# IO_Boardv3_RelayAlarm.net
KiCad netlist of a schematic drawn in Altium Designer
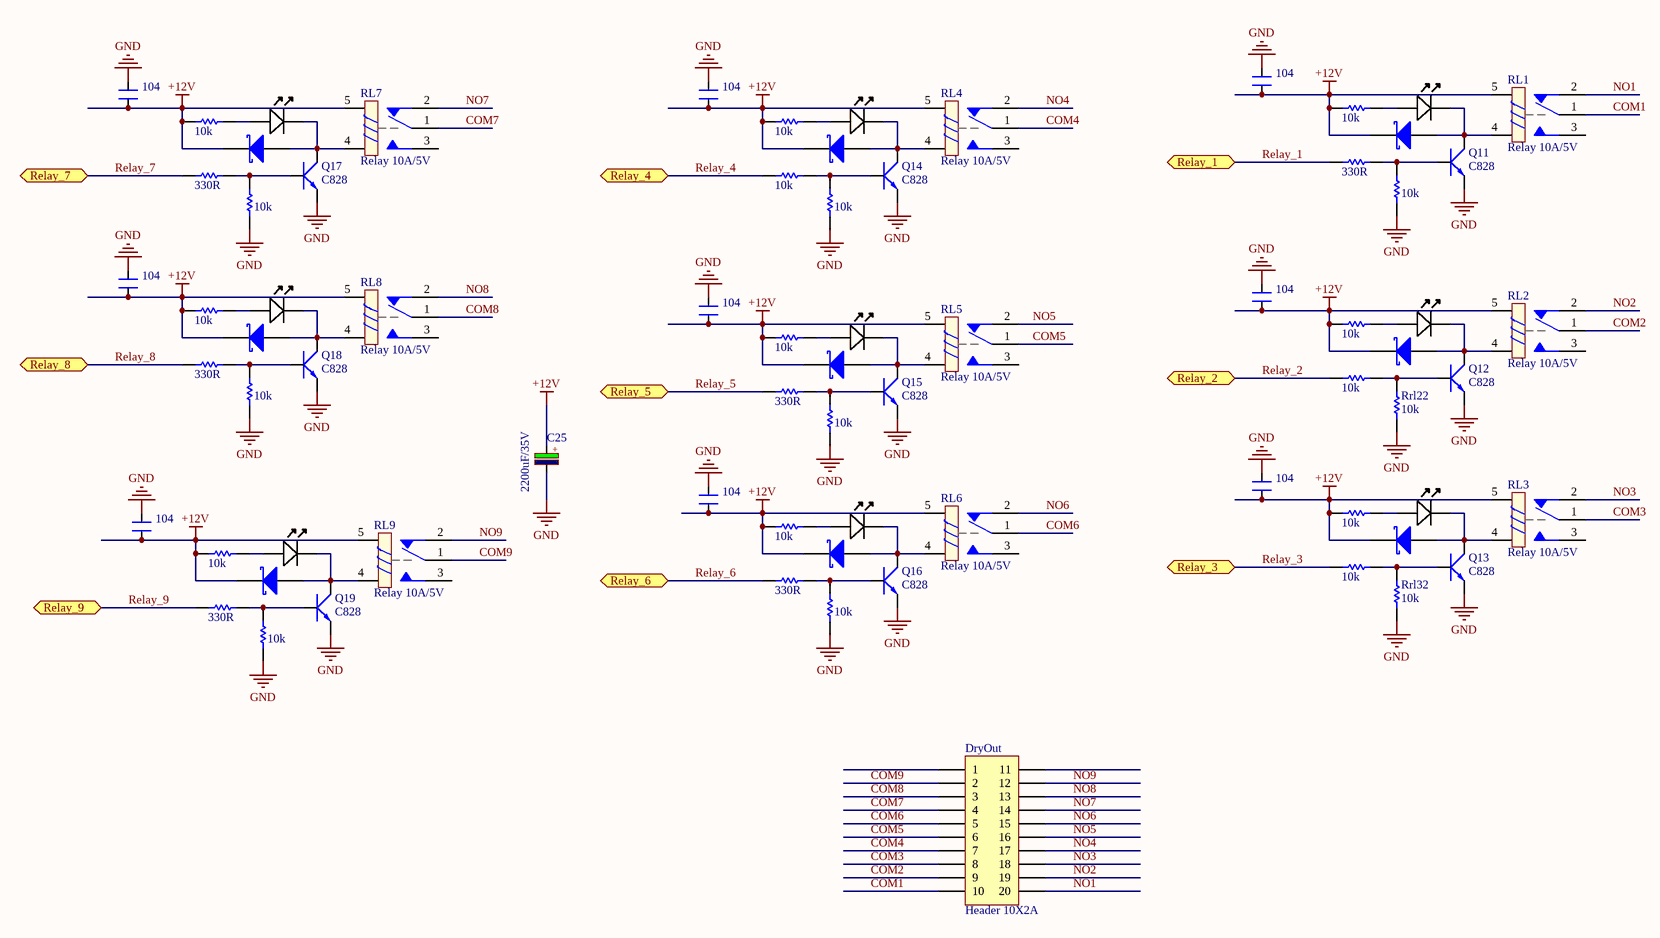
[diagram p0: IO_Boardv3_RelayAlarm.SchDoc]

(export (version "E")
  (design (tool "Eeschema 10.0.6"))
  (components
    (comp (ref "C25")
      (value "2200uF/35V")
      (footprint "heromap:CP_1000uF_25V")
      (description "Cap 1000uF/16V - 220uF/50V")
      (libsource (lib "heromap") (part "CP4"))
    )
    (comp (ref "Crl1")
      (value "104")
      (footprint "CAPC2012N_F")
      (fields (field (name "Comment") "CAP NP"))
      (libsource (lib "Tuan") (part "CAP NP"))
    )
    (comp (ref "Crl2")
      (value "104")
      (footprint "CAPC2012N_F")
      (fields (field (name "Comment") "CAP NP"))
      (libsource (lib "Tuan") (part "CAP NP"))
    )
    (comp (ref "Crl3")
      (value "104")
      (footprint "CAPC2012N_F")
      (fields (field (name "Comment") "CAP NP"))
      (libsource (lib "Tuan") (part "CAP NP"))
    )
    (comp (ref "Crl4")
      (value "104")
      (footprint "CAPC2012N_F")
      (fields (field (name "Comment") "CAP NP"))
      (libsource (lib "Tuan") (part "CAP NP"))
    )
    (comp (ref "Crl5")
      (value "104")
      (footprint "CAPC2012N_F")
      (fields (field (name "Comment") "CAP NP"))
      (libsource (lib "Tuan") (part "CAP NP"))
    )
    (comp (ref "Crl6")
      (value "104")
      (footprint "CAPC2012N_F")
      (fields (field (name "Comment") "CAP NP"))
      (libsource (lib "Tuan") (part "CAP NP"))
    )
    (comp (ref "Crl7")
      (value "104")
      (footprint "CAPC2012N_F")
      (fields (field (name "Comment") "CAP NP"))
      (libsource (lib "Tuan") (part "CAP NP"))
    )
    (comp (ref "Crl8")
      (value "104")
      (footprint "CAPC2012N_F")
      (fields (field (name "Comment") "CAP NP"))
      (libsource (lib "Tuan") (part "CAP NP"))
    )
    (comp (ref "Crl9")
      (value "104")
      (footprint "CAPC2012N_F")
      (fields (field (name "Comment") "CAP NP"))
      (libsource (lib "Tuan") (part "CAP NP"))
    )
    (comp (ref "D11") (value "Diode") (footprint "DO-214AC") (libsource (lib "Tuan") (part "Diode")))
    (comp (ref "D12") (value "Diode") (footprint "DO-214AC") (libsource (lib "Tuan") (part "Diode")))
    (comp (ref "D13") (value "Diode") (footprint "DO-214AC") (libsource (lib "Tuan") (part "Diode")))
    (comp (ref "D14") (value "Diode") (footprint "DO-214AC") (libsource (lib "Tuan") (part "Diode")))
    (comp (ref "D15") (value "Diode") (footprint "DO-214AC") (libsource (lib "Tuan") (part "Diode")))
    (comp (ref "D16") (value "Diode") (footprint "DO-214AC") (libsource (lib "Tuan") (part "Diode")))
    (comp (ref "D17") (value "Diode") (footprint "DO-214AC") (libsource (lib "Tuan") (part "Diode")))
    (comp (ref "D18") (value "Diode") (footprint "DO-214AC") (libsource (lib "Tuan") (part "Diode")))
    (comp (ref "D19") (value "Diode") (footprint "DO-214AC") (libsource (lib "Tuan") (part "Diode")))
    (comp (ref "DryOut")
      (value "Header 10X2A")
      (footprint "heromap:HDR2X10_CEN")
      (description "Header, 10-Pin, Dual row")
      (fields (field (name "PUBLISHER") "Altium Limited"))
      (libsource (lib "heromap") (part "Header 10X2A"))
    )
    (comp (ref "E1")
      (value "Blue")
      (footprint "LED-0805-A")
      (description "LED 0805 SMD Blue 100mcd 470nm")
      (libsource (lib "PBL - Light Sources") (part "LED_SMD_Blue_0805_100mcd"))
    )
    (comp (ref "E2")
      (value "Blue")
      (footprint "LED-0805-A")
      (description "LED 0805 SMD Blue 100mcd 470nm")
      (libsource (lib "PBL - Light Sources") (part "LED_SMD_Blue_0805_100mcd"))
    )
    (comp (ref "E3")
      (value "Blue")
      (footprint "LED-0805-A")
      (description "LED 0805 SMD Blue 100mcd 470nm")
      (libsource (lib "PBL - Light Sources") (part "LED_SMD_Blue_0805_100mcd"))
    )
    (comp (ref "E4")
      (value "Blue")
      (footprint "LED-0805-A")
      (description "LED 0805 SMD Blue 100mcd 470nm")
      (libsource (lib "PBL - Light Sources") (part "LED_SMD_Blue_0805_100mcd"))
    )
    (comp (ref "E5")
      (value "Blue")
      (footprint "LED-0805-A")
      (description "LED 0805 SMD Blue 100mcd 470nm")
      (libsource (lib "PBL - Light Sources") (part "LED_SMD_Blue_0805_100mcd"))
    )
    (comp (ref "E6")
      (value "Blue")
      (footprint "LED-0805-A")
      (description "LED 0805 SMD Blue 100mcd 470nm")
      (libsource (lib "PBL - Light Sources") (part "LED_SMD_Blue_0805_100mcd"))
    )
    (comp (ref "E7")
      (value "Blue")
      (footprint "LED-0805-A")
      (description "LED 0805 SMD Blue 100mcd 470nm")
      (libsource (lib "PBL - Light Sources") (part "LED_SMD_Blue_0805_100mcd"))
    )
    (comp (ref "E8")
      (value "Blue")
      (footprint "LED-0805-A")
      (description "LED 0805 SMD Blue 100mcd 470nm")
      (libsource (lib "PBL - Light Sources") (part "LED_SMD_Blue_0805_100mcd"))
    )
    (comp (ref "E9")
      (value "Blue")
      (footprint "LED-0805-A")
      (description "LED 0805 SMD Blue 100mcd 470nm")
      (libsource (lib "PBL - Light Sources") (part "LED_SMD_Blue_0805_100mcd"))
    )
    (comp (ref "Q11")
      (value "C828")
      (footprint "SOT23 TOP")
      (description "Transistor C828 C1815....")
      (libsource (lib "Tuan") (part "NPN"))
    )
    (comp (ref "Q12")
      (value "C828")
      (footprint "SOT23 TOP")
      (description "Transistor C828 C1815....")
      (libsource (lib "Tuan") (part "NPN"))
    )
    (comp (ref "Q13")
      (value "C828")
      (footprint "SOT23 TOP")
      (description "Transistor C828 C1815....")
      (libsource (lib "Tuan") (part "NPN"))
    )
    (comp (ref "Q14")
      (value "C828")
      (footprint "SOT23 TOP")
      (description "Transistor C828 C1815....")
      (libsource (lib "Tuan") (part "NPN"))
    )
    (comp (ref "Q15")
      (value "C828")
      (footprint "SOT23 TOP")
      (description "Transistor C828 C1815....")
      (libsource (lib "Tuan") (part "NPN"))
    )
    (comp (ref "Q16")
      (value "C828")
      (footprint "SOT23 TOP")
      (description "Transistor C828 C1815....")
      (libsource (lib "Tuan") (part "NPN"))
    )
    (comp (ref "Q17")
      (value "C828")
      (footprint "SOT23 TOP")
      (description "Transistor C828 C1815....")
      (libsource (lib "Tuan") (part "NPN"))
    )
    (comp (ref "Q18")
      (value "C828")
      (footprint "SOT23 TOP")
      (description "Transistor C828 C1815....")
      (libsource (lib "Tuan") (part "NPN"))
    )
    (comp (ref "Q19")
      (value "C828")
      (footprint "SOT23 TOP")
      (description "Transistor C828 C1815....")
      (libsource (lib "Tuan") (part "NPN"))
    )
    (comp (ref "RL1")
      (value "Relay 10A/5V")
      (footprint "RL_5PIN")
      (description "Relay SPDT,10A - 12VDC 5 Pin")
      (libsource (lib "syhaunguyen") (part "Relay 1"))
    )
    (comp (ref "RL2")
      (value "Relay 10A/5V")
      (footprint "RL_5PIN")
      (description "Relay SPDT,10A - 12VDC 5 Pin")
      (libsource (lib "syhaunguyen") (part "Relay 1"))
    )
    (comp (ref "RL3")
      (value "Relay 10A/5V")
      (footprint "RL_5PIN")
      (description "Relay SPDT,10A - 12VDC 5 Pin")
      (libsource (lib "syhaunguyen") (part "Relay 1"))
    )
    (comp (ref "RL4")
      (value "Relay 10A/5V")
      (footprint "RL_5PIN")
      (description "Relay SPDT,10A - 12VDC 5 Pin")
      (libsource (lib "syhaunguyen") (part "Relay 1"))
    )
    (comp (ref "RL5")
      (value "Relay 10A/5V")
      (footprint "RL_5PIN")
      (description "Relay SPDT,10A - 12VDC 5 Pin")
      (libsource (lib "syhaunguyen") (part "Relay 1"))
    )
    (comp (ref "RL6")
      (value "Relay 10A/5V")
      (footprint "RL_5PIN")
      (description "Relay SPDT,10A - 12VDC 5 Pin")
      (libsource (lib "syhaunguyen") (part "Relay 1"))
    )
    (comp (ref "RL7")
      (value "Relay 10A/5V")
      (footprint "RL_5PIN")
      (description "Relay SPDT,10A - 12VDC 5 Pin")
      (libsource (lib "syhaunguyen") (part "Relay 1"))
    )
    (comp (ref "RL8")
      (value "Relay 10A/5V")
      (footprint "RL_5PIN")
      (description "Relay SPDT,10A - 12VDC 5 Pin")
      (libsource (lib "syhaunguyen") (part "Relay 1"))
    )
    (comp (ref "RL9")
      (value "Relay 10A/5V")
      (footprint "RL_5PIN")
      (description "Relay SPDT,10A - 12VDC 5 Pin")
      (libsource (lib "syhaunguyen") (part "Relay 1"))
    )
    (comp (ref "Rl52")
      (value "10k")
      (footprint "RESC1608N_ZERO")
      (fields (field (name "Comment") "Res"))
      (libsource (lib "Tuan") (part "Res"))
    )
    (comp (ref "Rrl11")
      (value "330R")
      (footprint "RESC1608N_ZERO")
      (fields (field (name "Comment") "Res"))
      (libsource (lib "Tuan") (part "Res"))
    )
    (comp (ref "Rrl12")
      (value "10k")
      (footprint "RESC1608N_ZERO")
      (fields (field (name "Comment") "Res"))
      (libsource (lib "Tuan") (part "Res"))
    )
    (comp (ref "Rrl13")
      (value "10k")
      (footprint "RESC1608N_ZERO")
      (fields (field (name "Comment") "Res"))
      (libsource (lib "Tuan") (part "Res"))
    )
    (comp (ref "Rrl21")
      (value "10k")
      (footprint "RESC1608N_ZERO")
      (fields (field (name "Comment") "Res"))
      (libsource (lib "Tuan") (part "Res"))
    )
    (comp (ref "Rrl22")
      (value "10k")
      (footprint "RESC1608N_ZERO")
      (fields (field (name "Comment") "Res"))
      (libsource (lib "Tuan") (part "Res"))
    )
    (comp (ref "Rrl23")
      (value "10k")
      (footprint "RESC1608N_ZERO")
      (fields (field (name "Comment") "Res"))
      (libsource (lib "Tuan") (part "Res"))
    )
    (comp (ref "Rrl31")
      (value "10k")
      (footprint "RESC1608N_ZERO")
      (fields (field (name "Comment") "Res"))
      (libsource (lib "Tuan") (part "Res"))
    )
    (comp (ref "Rrl32")
      (value "10k")
      (footprint "RESC1608N_ZERO")
      (fields (field (name "Comment") "Res"))
      (libsource (lib "Tuan") (part "Res"))
    )
    (comp (ref "Rrl33")
      (value "10k")
      (footprint "RESC1608N_ZERO")
      (fields (field (name "Comment") "Res"))
      (libsource (lib "Tuan") (part "Res"))
    )
    (comp (ref "Rrl41")
      (value "10k")
      (footprint "RESC1608N_ZERO")
      (fields (field (name "Comment") "Res"))
      (libsource (lib "Tuan") (part "Res"))
    )
    (comp (ref "Rrl42")
      (value "10k")
      (footprint "RESC1608N_ZERO")
      (fields (field (name "Comment") "Res"))
      (libsource (lib "Tuan") (part "Res"))
    )
    (comp (ref "Rrl43")
      (value "10k")
      (footprint "RESC1608N_ZERO")
      (fields (field (name "Comment") "Res"))
      (libsource (lib "Tuan") (part "Res"))
    )
    (comp (ref "Rrl51")
      (value "330R")
      (footprint "RESC1608N_ZERO")
      (fields (field (name "Comment") "Res"))
      (libsource (lib "Tuan") (part "Res"))
    )
    (comp (ref "Rrl53")
      (value "10k")
      (footprint "RESC1608N_ZERO")
      (fields (field (name "Comment") "Res"))
      (libsource (lib "Tuan") (part "Res"))
    )
    (comp (ref "Rrl61")
      (value "330R")
      (footprint "RESC1608N_ZERO")
      (fields (field (name "Comment") "Res"))
      (libsource (lib "Tuan") (part "Res"))
    )
    (comp (ref "Rrl62")
      (value "10k")
      (footprint "RESC1608N_ZERO")
      (fields (field (name "Comment") "Res"))
      (libsource (lib "Tuan") (part "Res"))
    )
    (comp (ref "Rrl63")
      (value "10k")
      (footprint "RESC1608N_ZERO")
      (fields (field (name "Comment") "Res"))
      (libsource (lib "Tuan") (part "Res"))
    )
    (comp (ref "Rrl71")
      (value "330R")
      (footprint "RESC1608N_ZERO")
      (fields (field (name "Comment") "Res"))
      (libsource (lib "Tuan") (part "Res"))
    )
    (comp (ref "Rrl72")
      (value "10k")
      (footprint "RESC1608N_ZERO")
      (fields (field (name "Comment") "Res"))
      (libsource (lib "Tuan") (part "Res"))
    )
    (comp (ref "Rrl73")
      (value "10k")
      (footprint "RESC1608N_ZERO")
      (fields (field (name "Comment") "Res"))
      (libsource (lib "Tuan") (part "Res"))
    )
    (comp (ref "Rrl81")
      (value "330R")
      (footprint "RESC1608N_ZERO")
      (fields (field (name "Comment") "Res"))
      (libsource (lib "Tuan") (part "Res"))
    )
    (comp (ref "Rrl82")
      (value "10k")
      (footprint "RESC1608N_ZERO")
      (fields (field (name "Comment") "Res"))
      (libsource (lib "Tuan") (part "Res"))
    )
    (comp (ref "Rrl83")
      (value "10k")
      (footprint "RESC1608N_ZERO")
      (fields (field (name "Comment") "Res"))
      (libsource (lib "Tuan") (part "Res"))
    )
    (comp (ref "Rrl91")
      (value "330R")
      (footprint "RESC1608N_ZERO")
      (fields (field (name "Comment") "Res"))
      (libsource (lib "Tuan") (part "Res"))
    )
    (comp (ref "Rrl92")
      (value "10k")
      (footprint "RESC1608N_ZERO")
      (fields (field (name "Comment") "Res"))
      (libsource (lib "Tuan") (part "Res"))
    )
    (comp (ref "Rrl93")
      (value "10k")
      (footprint "RESC1608N_ZERO")
      (fields (field (name "Comment") "Res"))
      (libsource (lib "Tuan") (part "Res"))
    )
  )
  (nets
    (net (code "1") (name "+12V") (class "Default")
      (node (ref "C25") (pin "1") (pinfunction "1_1") (pintype "passive"))
      (node (ref "Crl1") (pin "1") (pinfunction "1_1") (pintype "passive"))
      (node (ref "Crl2") (pin "1") (pinfunction "1_1") (pintype "passive"))
      (node (ref "Crl3") (pin "1") (pinfunction "1_1") (pintype "passive"))
      (node (ref "Crl4") (pin "1") (pinfunction "1_1") (pintype "passive"))
      (node (ref "Crl5") (pin "1") (pinfunction "1_1") (pintype "passive"))
      (node (ref "Crl6") (pin "1") (pinfunction "1_1") (pintype "passive"))
      (node (ref "Crl7") (pin "1") (pinfunction "1_1") (pintype "passive"))
      (node (ref "Crl8") (pin "1") (pinfunction "1_1") (pintype "passive"))
      (node (ref "Crl9") (pin "1") (pinfunction "1_1") (pintype "passive"))
      (node (ref "D11") (pin "2") (pinfunction "K_2") (pintype "passive"))
      (node (ref "D12") (pin "2") (pinfunction "K_2") (pintype "passive"))
      (node (ref "D13") (pin "2") (pinfunction "K_2") (pintype "passive"))
      (node (ref "D14") (pin "2") (pinfunction "K_2") (pintype "passive"))
      (node (ref "D15") (pin "2") (pinfunction "K_2") (pintype "passive"))
      (node (ref "D16") (pin "2") (pinfunction "K_2") (pintype "passive"))
      (node (ref "D17") (pin "2") (pinfunction "K_2") (pintype "passive"))
      (node (ref "D18") (pin "2") (pinfunction "K_2") (pintype "passive"))
      (node (ref "D19") (pin "2") (pinfunction "K_2") (pintype "passive"))
      (node (ref "RL1") (pin "5") (pinfunction "5_5") (pintype "passive"))
      (node (ref "RL2") (pin "5") (pinfunction "5_5") (pintype "passive"))
      (node (ref "RL3") (pin "5") (pinfunction "5_5") (pintype "passive"))
      (node (ref "RL4") (pin "5") (pinfunction "5_5") (pintype "passive"))
      (node (ref "RL5") (pin "5") (pinfunction "5_5") (pintype "passive"))
      (node (ref "RL6") (pin "5") (pinfunction "5_5") (pintype "passive"))
      (node (ref "RL7") (pin "5") (pinfunction "5_5") (pintype "passive"))
      (node (ref "RL8") (pin "5") (pinfunction "5_5") (pintype "passive"))
      (node (ref "RL9") (pin "5") (pinfunction "5_5") (pintype "passive"))
      (node (ref "Rrl13") (pin "2") (pinfunction "2_2") (pintype "passive"))
      (node (ref "Rrl23") (pin "2") (pinfunction "2_2") (pintype "passive"))
      (node (ref "Rrl33") (pin "2") (pinfunction "2_2") (pintype "passive"))
      (node (ref "Rrl43") (pin "2") (pinfunction "2_2") (pintype "passive"))
      (node (ref "Rrl53") (pin "2") (pinfunction "2_2") (pintype "passive"))
      (node (ref "Rrl63") (pin "2") (pinfunction "2_2") (pintype "passive"))
      (node (ref "Rrl73") (pin "2") (pinfunction "2_2") (pintype "passive"))
      (node (ref "Rrl83") (pin "2") (pinfunction "2_2") (pintype "passive"))
      (node (ref "Rrl93") (pin "2") (pinfunction "2_2") (pintype "passive"))
    )
    (net (code "2") (name "/COM1") (class "Default")
      (node (ref "DryOut") (pin "10") (pinfunction "10_10") (pintype "passive"))
      (node (ref "RL1") (pin "1") (pinfunction "1_1") (pintype "passive"))
    )
    (net (code "3") (name "/COM2") (class "Default")
      (node (ref "DryOut") (pin "9") (pinfunction "9_9") (pintype "passive"))
      (node (ref "RL2") (pin "1") (pinfunction "1_1") (pintype "passive"))
    )
    (net (code "4") (name "/COM3") (class "Default")
      (node (ref "DryOut") (pin "8") (pinfunction "8_8") (pintype "passive"))
      (node (ref "RL3") (pin "1") (pinfunction "1_1") (pintype "passive"))
    )
    (net (code "5") (name "/COM4") (class "Default")
      (node (ref "DryOut") (pin "7") (pinfunction "7_7") (pintype "passive"))
      (node (ref "RL4") (pin "1") (pinfunction "1_1") (pintype "passive"))
    )
    (net (code "6") (name "/COM5") (class "Default")
      (node (ref "DryOut") (pin "6") (pinfunction "6_6") (pintype "passive"))
      (node (ref "RL5") (pin "1") (pinfunction "1_1") (pintype "passive"))
    )
    (net (code "7") (name "/COM6") (class "Default")
      (node (ref "DryOut") (pin "5") (pinfunction "5_5") (pintype "passive"))
      (node (ref "RL6") (pin "1") (pinfunction "1_1") (pintype "passive"))
    )
    (net (code "8") (name "/COM7") (class "Default")
      (node (ref "DryOut") (pin "4") (pinfunction "4_4") (pintype "passive"))
      (node (ref "RL7") (pin "1") (pinfunction "1_1") (pintype "passive"))
    )
    (net (code "9") (name "/COM8") (class "Default")
      (node (ref "DryOut") (pin "3") (pinfunction "3_3") (pintype "passive"))
      (node (ref "RL8") (pin "1") (pinfunction "1_1") (pintype "passive"))
    )
    (net (code "10") (name "/COM9") (class "Default")
      (node (ref "DryOut") (pin "2") (pinfunction "2_2") (pintype "passive"))
      (node (ref "RL9") (pin "1") (pinfunction "1_1") (pintype "passive"))
    )
    (net (code "11") (name "/NO1") (class "Default")
      (node (ref "DryOut") (pin "20") (pinfunction "20_20") (pintype "passive"))
      (node (ref "RL1") (pin "2") (pinfunction "2_2") (pintype "passive"))
    )
    (net (code "12") (name "/NO2") (class "Default")
      (node (ref "DryOut") (pin "19") (pinfunction "19_19") (pintype "passive"))
      (node (ref "RL2") (pin "2") (pinfunction "2_2") (pintype "passive"))
    )
    (net (code "13") (name "/NO3") (class "Default")
      (node (ref "DryOut") (pin "18") (pinfunction "18_18") (pintype "passive"))
      (node (ref "RL3") (pin "2") (pinfunction "2_2") (pintype "passive"))
    )
    (net (code "14") (name "/NO4") (class "Default")
      (node (ref "DryOut") (pin "17") (pinfunction "17_17") (pintype "passive"))
      (node (ref "RL4") (pin "2") (pinfunction "2_2") (pintype "passive"))
    )
    (net (code "15") (name "/NO5") (class "Default")
      (node (ref "DryOut") (pin "16") (pinfunction "16_16") (pintype "passive"))
      (node (ref "RL5") (pin "2") (pinfunction "2_2") (pintype "passive"))
    )
    (net (code "16") (name "/NO6") (class "Default")
      (node (ref "DryOut") (pin "15") (pinfunction "15_15") (pintype "passive"))
      (node (ref "RL6") (pin "2") (pinfunction "2_2") (pintype "passive"))
    )
    (net (code "17") (name "/NO7") (class "Default")
      (node (ref "DryOut") (pin "14") (pinfunction "14_14") (pintype "passive"))
      (node (ref "RL7") (pin "2") (pinfunction "2_2") (pintype "passive"))
    )
    (net (code "18") (name "/NO8") (class "Default")
      (node (ref "DryOut") (pin "13") (pinfunction "13_13") (pintype "passive"))
      (node (ref "RL8") (pin "2") (pinfunction "2_2") (pintype "passive"))
    )
    (net (code "19") (name "/NO9") (class "Default")
      (node (ref "DryOut") (pin "12") (pinfunction "12_12") (pintype "passive"))
      (node (ref "RL9") (pin "2") (pinfunction "2_2") (pintype "passive"))
    )
    (net (code "20") (name "/Relay_1") (class "Default")
      (node (ref "Rrl11") (pin "1") (pinfunction "1_1") (pintype "passive"))
    )
    (net (code "21") (name "/Relay_2") (class "Default")
      (node (ref "Rrl21") (pin "1") (pinfunction "1_1") (pintype "passive"))
    )
    (net (code "22") (name "/Relay_3") (class "Default")
      (node (ref "Rrl31") (pin "1") (pinfunction "1_1") (pintype "passive"))
    )
    (net (code "23") (name "/Relay_4") (class "Default")
      (node (ref "Rrl41") (pin "1") (pinfunction "1_1") (pintype "passive"))
    )
    (net (code "24") (name "/Relay_5") (class "Default")
      (node (ref "Rrl51") (pin "1") (pinfunction "1_1") (pintype "passive"))
    )
    (net (code "25") (name "/Relay_6") (class "Default")
      (node (ref "Rrl61") (pin "1") (pinfunction "1_1") (pintype "passive"))
    )
    (net (code "26") (name "/Relay_7") (class "Default")
      (node (ref "Rrl71") (pin "1") (pinfunction "1_1") (pintype "passive"))
    )
    (net (code "27") (name "/Relay_8") (class "Default")
      (node (ref "Rrl81") (pin "1") (pinfunction "1_1") (pintype "passive"))
    )
    (net (code "28") (name "/Relay_9") (class "Default")
      (node (ref "Rrl91") (pin "1") (pinfunction "1_1") (pintype "passive"))
    )
    (net (code "29") (name "GND") (class "Default")
      (node (ref "C25") (pin "2") (pinfunction "2_2") (pintype "passive"))
      (node (ref "Crl1") (pin "2") (pinfunction "2_2") (pintype "passive"))
      (node (ref "Crl2") (pin "2") (pinfunction "2_2") (pintype "passive"))
      (node (ref "Crl3") (pin "2") (pinfunction "2_2") (pintype "passive"))
      (node (ref "Crl4") (pin "2") (pinfunction "2_2") (pintype "passive"))
      (node (ref "Crl5") (pin "2") (pinfunction "2_2") (pintype "passive"))
      (node (ref "Crl6") (pin "2") (pinfunction "2_2") (pintype "passive"))
      (node (ref "Crl7") (pin "2") (pinfunction "2_2") (pintype "passive"))
      (node (ref "Crl8") (pin "2") (pinfunction "2_2") (pintype "passive"))
      (node (ref "Crl9") (pin "2") (pinfunction "2_2") (pintype "passive"))
      (node (ref "Q11") (pin "3") (pinfunction "E_3") (pintype "passive"))
      (node (ref "Q12") (pin "3") (pinfunction "E_3") (pintype "passive"))
      (node (ref "Q13") (pin "3") (pinfunction "E_3") (pintype "passive"))
      (node (ref "Q14") (pin "3") (pinfunction "E_3") (pintype "passive"))
      (node (ref "Q15") (pin "3") (pinfunction "E_3") (pintype "passive"))
      (node (ref "Q16") (pin "3") (pinfunction "E_3") (pintype "passive"))
      (node (ref "Q17") (pin "3") (pinfunction "E_3") (pintype "passive"))
      (node (ref "Q18") (pin "3") (pinfunction "E_3") (pintype "passive"))
      (node (ref "Q19") (pin "3") (pinfunction "E_3") (pintype "passive"))
      (node (ref "Rl52") (pin "1") (pinfunction "1_1") (pintype "passive"))
      (node (ref "Rrl12") (pin "1") (pinfunction "1_1") (pintype "passive"))
      (node (ref "Rrl22") (pin "1") (pinfunction "1_1") (pintype "passive"))
      (node (ref "Rrl32") (pin "1") (pinfunction "1_1") (pintype "passive"))
      (node (ref "Rrl42") (pin "1") (pinfunction "1_1") (pintype "passive"))
      (node (ref "Rrl62") (pin "1") (pinfunction "1_1") (pintype "passive"))
      (node (ref "Rrl72") (pin "1") (pinfunction "1_1") (pintype "passive"))
      (node (ref "Rrl82") (pin "1") (pinfunction "1_1") (pintype "passive"))
      (node (ref "Rrl92") (pin "1") (pinfunction "1_1") (pintype "passive"))
    )
    (net (code "30") (name "Net-(D11-A)") (class "Default")
      (node (ref "D11") (pin "1") (pinfunction "A_1") (pintype "passive"))
      (node (ref "E1") (pin "K") (pinfunction "K_K") (pintype "passive"))
      (node (ref "Q11") (pin "2") (pinfunction "C_2") (pintype "passive"))
      (node (ref "RL1") (pin "4") (pinfunction "4_4") (pintype "passive"))
    )
    (net (code "31") (name "Net-(D12-A)") (class "Default")
      (node (ref "D12") (pin "1") (pinfunction "A_1") (pintype "passive"))
      (node (ref "E2") (pin "K") (pinfunction "K_K") (pintype "passive"))
      (node (ref "Q12") (pin "2") (pinfunction "C_2") (pintype "passive"))
      (node (ref "RL2") (pin "4") (pinfunction "4_4") (pintype "passive"))
    )
    (net (code "32") (name "Net-(D13-A)") (class "Default")
      (node (ref "D13") (pin "1") (pinfunction "A_1") (pintype "passive"))
      (node (ref "E3") (pin "K") (pinfunction "K_K") (pintype "passive"))
      (node (ref "Q13") (pin "2") (pinfunction "C_2") (pintype "passive"))
      (node (ref "RL3") (pin "4") (pinfunction "4_4") (pintype "passive"))
    )
    (net (code "33") (name "Net-(D14-A)") (class "Default")
      (node (ref "D14") (pin "1") (pinfunction "A_1") (pintype "passive"))
      (node (ref "E4") (pin "K") (pinfunction "K_K") (pintype "passive"))
      (node (ref "Q14") (pin "2") (pinfunction "C_2") (pintype "passive"))
      (node (ref "RL4") (pin "4") (pinfunction "4_4") (pintype "passive"))
    )
    (net (code "34") (name "Net-(D15-A)") (class "Default")
      (node (ref "D15") (pin "1") (pinfunction "A_1") (pintype "passive"))
      (node (ref "E5") (pin "K") (pinfunction "K_K") (pintype "passive"))
      (node (ref "Q15") (pin "2") (pinfunction "C_2") (pintype "passive"))
      (node (ref "RL5") (pin "4") (pinfunction "4_4") (pintype "passive"))
    )
    (net (code "35") (name "Net-(D16-A)") (class "Default")
      (node (ref "D16") (pin "1") (pinfunction "A_1") (pintype "passive"))
      (node (ref "E6") (pin "K") (pinfunction "K_K") (pintype "passive"))
      (node (ref "Q16") (pin "2") (pinfunction "C_2") (pintype "passive"))
      (node (ref "RL6") (pin "4") (pinfunction "4_4") (pintype "passive"))
    )
    (net (code "36") (name "Net-(D17-A)") (class "Default")
      (node (ref "D17") (pin "1") (pinfunction "A_1") (pintype "passive"))
      (node (ref "E7") (pin "K") (pinfunction "K_K") (pintype "passive"))
      (node (ref "Q17") (pin "2") (pinfunction "C_2") (pintype "passive"))
      (node (ref "RL7") (pin "4") (pinfunction "4_4") (pintype "passive"))
    )
    (net (code "37") (name "Net-(D18-A)") (class "Default")
      (node (ref "D18") (pin "1") (pinfunction "A_1") (pintype "passive"))
      (node (ref "E8") (pin "K") (pinfunction "K_K") (pintype "passive"))
      (node (ref "Q18") (pin "2") (pinfunction "C_2") (pintype "passive"))
      (node (ref "RL8") (pin "4") (pinfunction "4_4") (pintype "passive"))
    )
    (net (code "38") (name "Net-(D19-A)") (class "Default")
      (node (ref "D19") (pin "1") (pinfunction "A_1") (pintype "passive"))
      (node (ref "E9") (pin "K") (pinfunction "K_K") (pintype "passive"))
      (node (ref "Q19") (pin "2") (pinfunction "C_2") (pintype "passive"))
      (node (ref "RL9") (pin "4") (pinfunction "4_4") (pintype "passive"))
    )
    (net (code "39") (name "Net-(E1-PadA)") (class "Default")
      (node (ref "E1") (pin "A") (pinfunction "A_A") (pintype "passive"))
      (node (ref "Rrl13") (pin "1") (pinfunction "1_1") (pintype "passive"))
    )
    (net (code "40") (name "Net-(E2-PadA)") (class "Default")
      (node (ref "E2") (pin "A") (pinfunction "A_A") (pintype "passive"))
      (node (ref "Rrl23") (pin "1") (pinfunction "1_1") (pintype "passive"))
    )
    (net (code "41") (name "Net-(E3-PadA)") (class "Default")
      (node (ref "E3") (pin "A") (pinfunction "A_A") (pintype "passive"))
      (node (ref "Rrl33") (pin "1") (pinfunction "1_1") (pintype "passive"))
    )
    (net (code "42") (name "Net-(E4-PadA)") (class "Default")
      (node (ref "E4") (pin "A") (pinfunction "A_A") (pintype "passive"))
      (node (ref "Rrl43") (pin "1") (pinfunction "1_1") (pintype "passive"))
    )
    (net (code "43") (name "Net-(E5-PadA)") (class "Default")
      (node (ref "E5") (pin "A") (pinfunction "A_A") (pintype "passive"))
      (node (ref "Rrl53") (pin "1") (pinfunction "1_1") (pintype "passive"))
    )
    (net (code "44") (name "Net-(E6-PadA)") (class "Default")
      (node (ref "E6") (pin "A") (pinfunction "A_A") (pintype "passive"))
      (node (ref "Rrl63") (pin "1") (pinfunction "1_1") (pintype "passive"))
    )
    (net (code "45") (name "Net-(E7-PadA)") (class "Default")
      (node (ref "E7") (pin "A") (pinfunction "A_A") (pintype "passive"))
      (node (ref "Rrl73") (pin "1") (pinfunction "1_1") (pintype "passive"))
    )
    (net (code "46") (name "Net-(E8-PadA)") (class "Default")
      (node (ref "E8") (pin "A") (pinfunction "A_A") (pintype "passive"))
      (node (ref "Rrl83") (pin "1") (pinfunction "1_1") (pintype "passive"))
    )
    (net (code "47") (name "Net-(E9-PadA)") (class "Default")
      (node (ref "E9") (pin "A") (pinfunction "A_A") (pintype "passive"))
      (node (ref "Rrl93") (pin "1") (pinfunction "1_1") (pintype "passive"))
    )
    (net (code "48") (name "Net-(Q11-B)") (class "Default")
      (node (ref "Q11") (pin "1") (pinfunction "B_1") (pintype "passive"))
      (node (ref "Rrl11") (pin "2") (pinfunction "2_2") (pintype "passive"))
      (node (ref "Rrl12") (pin "2") (pinfunction "2_2") (pintype "passive"))
    )
    (net (code "49") (name "Net-(Q12-B)") (class "Default")
      (node (ref "Q12") (pin "1") (pinfunction "B_1") (pintype "passive"))
      (node (ref "Rrl21") (pin "2") (pinfunction "2_2") (pintype "passive"))
      (node (ref "Rrl22") (pin "2") (pinfunction "2_2") (pintype "passive"))
    )
    (net (code "50") (name "Net-(Q13-B)") (class "Default")
      (node (ref "Q13") (pin "1") (pinfunction "B_1") (pintype "passive"))
      (node (ref "Rrl31") (pin "2") (pinfunction "2_2") (pintype "passive"))
      (node (ref "Rrl32") (pin "2") (pinfunction "2_2") (pintype "passive"))
    )
    (net (code "51") (name "Net-(Q14-B)") (class "Default")
      (node (ref "Q14") (pin "1") (pinfunction "B_1") (pintype "passive"))
      (node (ref "Rrl41") (pin "2") (pinfunction "2_2") (pintype "passive"))
      (node (ref "Rrl42") (pin "2") (pinfunction "2_2") (pintype "passive"))
    )
    (net (code "52") (name "Net-(Q15-B)") (class "Default")
      (node (ref "Q15") (pin "1") (pinfunction "B_1") (pintype "passive"))
      (node (ref "Rl52") (pin "2") (pinfunction "2_2") (pintype "passive"))
      (node (ref "Rrl51") (pin "2") (pinfunction "2_2") (pintype "passive"))
    )
    (net (code "53") (name "Net-(Q16-B)") (class "Default")
      (node (ref "Q16") (pin "1") (pinfunction "B_1") (pintype "passive"))
      (node (ref "Rrl61") (pin "2") (pinfunction "2_2") (pintype "passive"))
      (node (ref "Rrl62") (pin "2") (pinfunction "2_2") (pintype "passive"))
    )
    (net (code "54") (name "Net-(Q17-B)") (class "Default")
      (node (ref "Q17") (pin "1") (pinfunction "B_1") (pintype "passive"))
      (node (ref "Rrl71") (pin "2") (pinfunction "2_2") (pintype "passive"))
      (node (ref "Rrl72") (pin "2") (pinfunction "2_2") (pintype "passive"))
    )
    (net (code "55") (name "Net-(Q18-B)") (class "Default")
      (node (ref "Q18") (pin "1") (pinfunction "B_1") (pintype "passive"))
      (node (ref "Rrl81") (pin "2") (pinfunction "2_2") (pintype "passive"))
      (node (ref "Rrl82") (pin "2") (pinfunction "2_2") (pintype "passive"))
    )
    (net (code "56") (name "Net-(Q19-B)") (class "Default")
      (node (ref "Q19") (pin "1") (pinfunction "B_1") (pintype "passive"))
      (node (ref "Rrl91") (pin "2") (pinfunction "2_2") (pintype "passive"))
      (node (ref "Rrl92") (pin "2") (pinfunction "2_2") (pintype "passive"))
    )
    (net (code "57") (name "unconnected-(DryOut-Pad1)") (class "Default")
      (node (ref "DryOut") (pin "1") (pinfunction "1_1") (pintype "passive"))
    )
    (net (code "58") (name "unconnected-(DryOut-Pad11)") (class "Default")
      (node (ref "DryOut") (pin "11") (pinfunction "11_11") (pintype "passive"))
    )
    (net (code "59") (name "unconnected-(RL1-Pad3)") (class "Default")
      (node (ref "RL1") (pin "3") (pinfunction "3_3") (pintype "passive"))
    )
    (net (code "60") (name "unconnected-(RL2-Pad3)") (class "Default")
      (node (ref "RL2") (pin "3") (pinfunction "3_3") (pintype "passive"))
    )
    (net (code "61") (name "unconnected-(RL3-Pad3)") (class "Default")
      (node (ref "RL3") (pin "3") (pinfunction "3_3") (pintype "passive"))
    )
    (net (code "62") (name "unconnected-(RL4-Pad3)") (class "Default")
      (node (ref "RL4") (pin "3") (pinfunction "3_3") (pintype "passive"))
    )
    (net (code "63") (name "unconnected-(RL5-Pad3)") (class "Default")
      (node (ref "RL5") (pin "3") (pinfunction "3_3") (pintype "passive"))
    )
    (net (code "64") (name "unconnected-(RL6-Pad3)") (class "Default")
      (node (ref "RL6") (pin "3") (pinfunction "3_3") (pintype "passive"))
    )
    (net (code "65") (name "unconnected-(RL7-Pad3)") (class "Default")
      (node (ref "RL7") (pin "3") (pinfunction "3_3") (pintype "passive"))
    )
    (net (code "66") (name "unconnected-(RL8-Pad3)") (class "Default")
      (node (ref "RL8") (pin "3") (pinfunction "3_3") (pintype "passive"))
    )
    (net (code "67") (name "unconnected-(RL9-Pad3)") (class "Default")
      (node (ref "RL9") (pin "3") (pinfunction "3_3") (pintype "passive"))
    )
  )
)
